# LSM303_breakout_board-v12.net
KiCad netlist of a schematic drawn in EAGLE
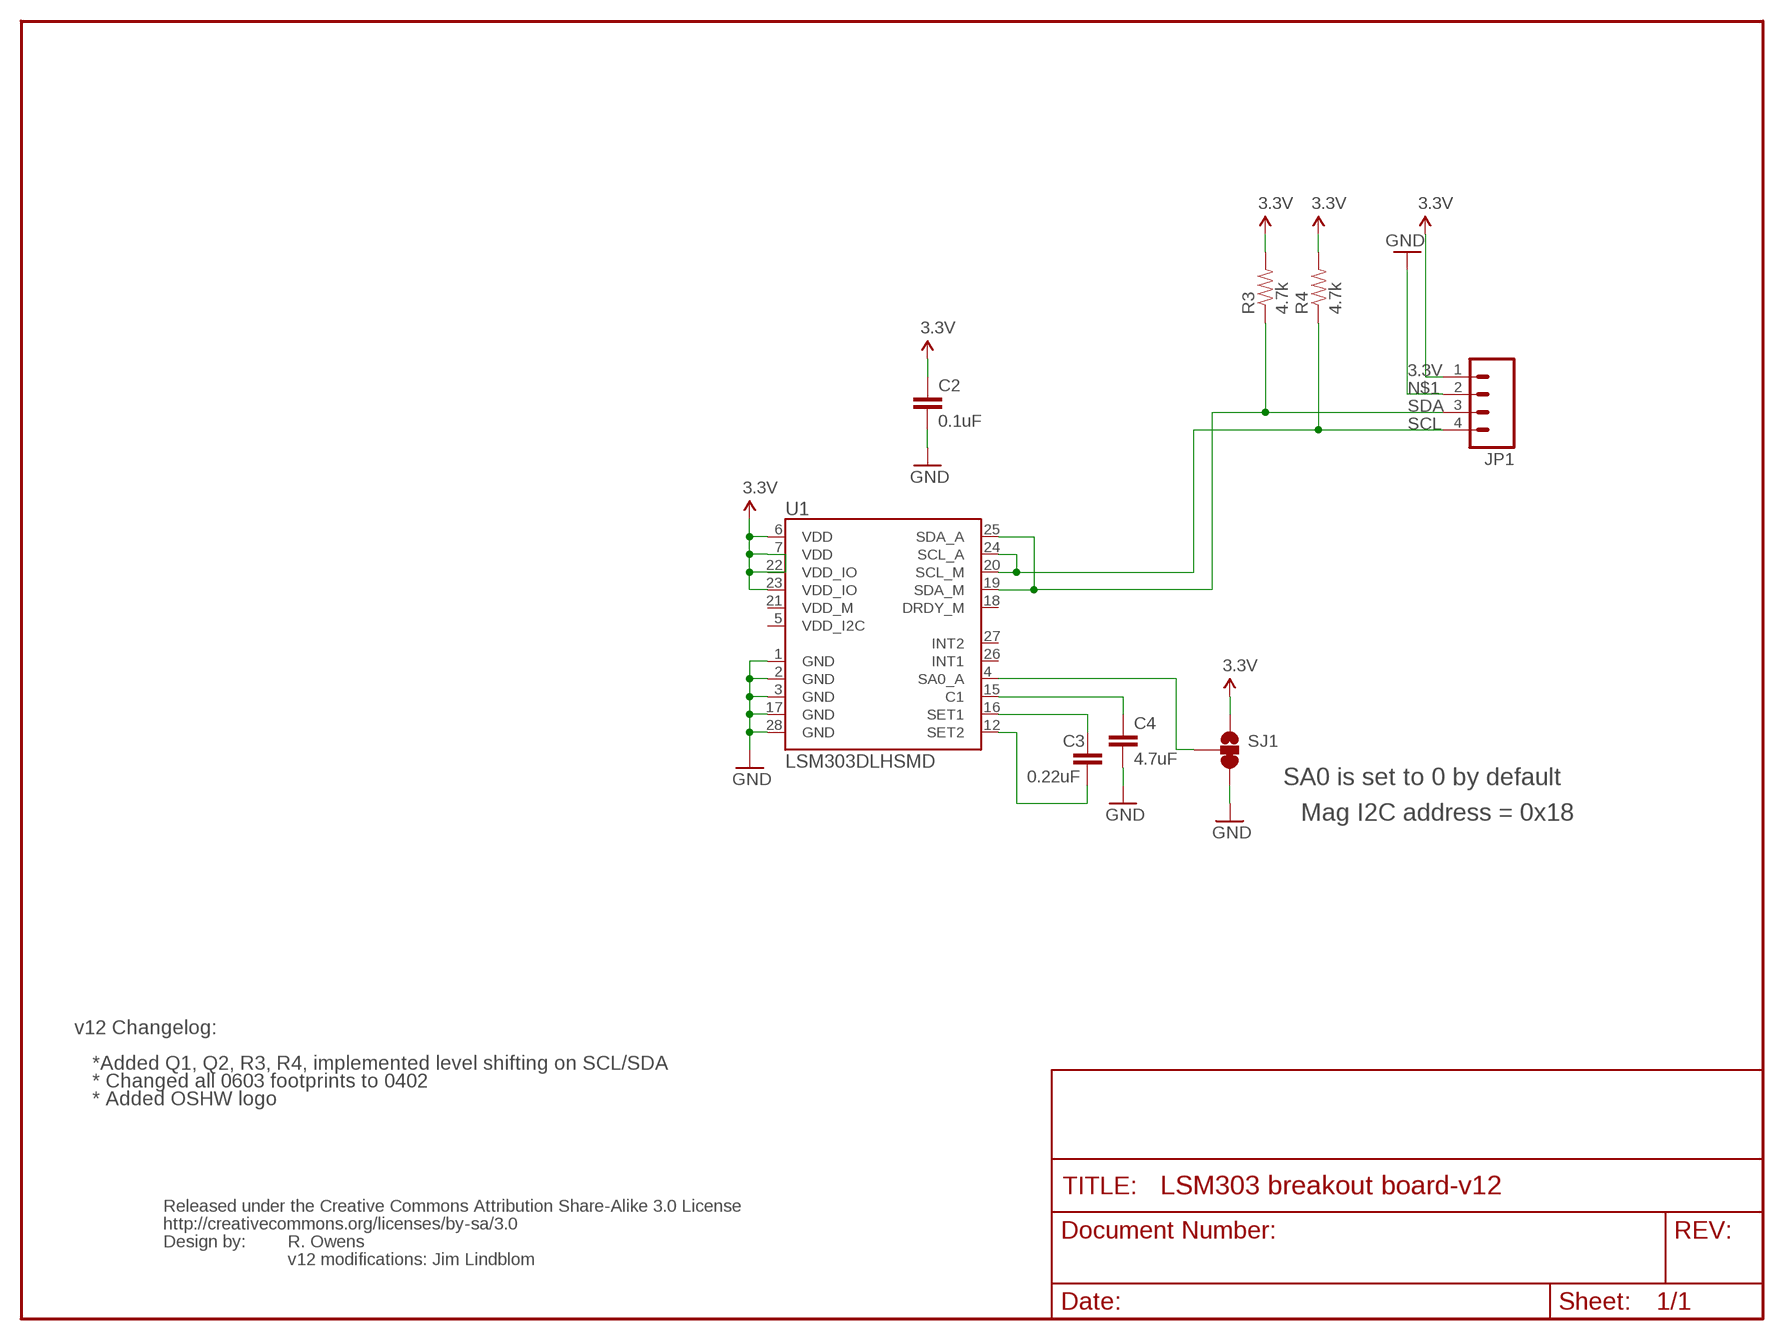
[diagram p0: schematic, sheet 1]

(export (version "E")
  (design (tool "Eeschema 10.0.6"))
  (components
    (comp (ref "C2")
      (value "0.1uF")
      (footprint "eagle-import:0603-CAP")
      (libsource (lib "eagle-import") (part "CAP0603-CAP"))
    )
    (comp (ref "C3")
      (value "0.22uF")
      (footprint "eagle-import:0603-CAP")
      (libsource (lib "eagle-import") (part "CAP0603-CAP"))
    )
    (comp (ref "C4")
      (value "4.7uF")
      (footprint "eagle-import:1206")
      (libsource (lib "eagle-import") (part "CAP1206"))
    )
    (comp (ref "JP1")
      (value "M04PTH")
      (footprint "eagle-import:1X04")
      (libsource (lib "eagle-import") (part "M04PTH"))
    )
    (comp (ref "R3")
      (value "4.7k")
      (footprint "eagle-import:0805")
      (libsource (lib "eagle-import") (part "RESISTOR0805-RES"))
    )
    (comp (ref "R4")
      (value "4.7k")
      (footprint "eagle-import:0805")
      (libsource (lib "eagle-import") (part "RESISTOR0805-RES"))
    )
    (comp (ref "SJ1")
      (value "SOLDERJUMPER_2WAYPASTE2&3")
      (footprint "eagle-import:SJ_3_PASTE2&3")
      (libsource (lib "eagle-import") (part "SOLDERJUMPER_2WAYPASTE2&3"))
    )
    (comp (ref "U$5")
      (value "CREATIVE_COMMONS")
      (footprint "eagle-import:CREATIVE_COMMONS")
      (libsource (lib "eagle-import") (part "CREATIVE_COMMONS"))
    )
    (comp (ref "U1")
      (value "LSM303DLHSMD")
      (footprint "eagle-import:LGA28-5X5")
      (libsource (lib "eagle-import") (part "LSM303DLHSMD"))
    )
  )
  (nets
    (net (code "1") (name "/SCL") (class "Default")
      (node (ref "JP1") (pin "4") (pinfunction "4_4") (pintype "passive"))
      (node (ref "R4") (pin "1") (pinfunction "1_1") (pintype "passive"))
      (node (ref "U1") (pin "20") (pinfunction "SCL_M_20") (pintype "bidirectional"))
      (node (ref "U1") (pin "24") (pinfunction "SCL_A_24") (pintype "bidirectional"))
    )
    (net (code "2") (name "/SDA") (class "Default")
      (node (ref "JP1") (pin "3") (pinfunction "3_3") (pintype "passive"))
      (node (ref "R3") (pin "1") (pinfunction "1_1") (pintype "passive"))
      (node (ref "U1") (pin "19") (pinfunction "SDA_M_19") (pintype "bidirectional"))
      (node (ref "U1") (pin "25") (pinfunction "SDA_A_25") (pintype "bidirectional"))
    )
    (net (code "3") (name "3.3V") (class "Default")
      (node (ref "C2") (pin "1") (pinfunction "1_1") (pintype "passive"))
      (node (ref "JP1") (pin "1") (pinfunction "1_1") (pintype "passive"))
      (node (ref "R3") (pin "2") (pinfunction "2_2") (pintype "passive"))
      (node (ref "R4") (pin "2") (pinfunction "2_2") (pintype "passive"))
      (node (ref "SJ1") (pin "1") (pinfunction "1_1") (pintype "passive"))
      (node (ref "U1") (pin "23") (pinfunction "VDD_IO_23") (pintype "bidirectional"))
      (node (ref "U1") (pin "6") (pinfunction "VDD_6") (pintype "bidirectional"))
      (node (ref "U1") (pin "7") (pinfunction "VDD_7") (pintype "bidirectional"))
    )
    (net (code "4") (name "GND") (class "Default")
      (node (ref "C2") (pin "2") (pinfunction "2_2") (pintype "passive"))
      (node (ref "C4") (pin "2") (pinfunction "2_2") (pintype "passive"))
      (node (ref "JP1") (pin "2") (pinfunction "2_2") (pintype "passive"))
      (node (ref "SJ1") (pin "3") (pinfunction "3_3") (pintype "passive"))
      (node (ref "U1") (pin "1") (pinfunction "GND_1") (pintype "bidirectional"))
      (node (ref "U1") (pin "17") (pinfunction "GND_17") (pintype "bidirectional"))
      (node (ref "U1") (pin "2") (pinfunction "GND_2") (pintype "bidirectional"))
      (node (ref "U1") (pin "28") (pinfunction "GND_28") (pintype "bidirectional"))
      (node (ref "U1") (pin "3") (pinfunction "GND_3") (pintype "bidirectional"))
    )
    (net (code "5") (name "Net-(U1-C1)") (class "Default")
      (node (ref "C4") (pin "1") (pinfunction "1_1") (pintype "passive"))
      (node (ref "U1") (pin "15") (pinfunction "C1_15") (pintype "bidirectional"))
    )
    (net (code "6") (name "Net-(U1-SA0_A)") (class "Default")
      (node (ref "SJ1") (pin "2") (pinfunction "2_2") (pintype "passive"))
      (node (ref "U1") (pin "4") (pinfunction "SA0_A_4") (pintype "bidirectional"))
    )
    (net (code "7") (name "Net-(U1-SET1)") (class "Default")
      (node (ref "C3") (pin "1") (pinfunction "1_1") (pintype "passive"))
      (node (ref "U1") (pin "16") (pinfunction "SET1_16") (pintype "bidirectional"))
    )
    (net (code "8") (name "Net-(U1-SET2)") (class "Default")
      (node (ref "C3") (pin "2") (pinfunction "2_2") (pintype "passive"))
      (node (ref "U1") (pin "12") (pinfunction "SET2_12") (pintype "bidirectional"))
    )
    (net (code "9") (name "unconnected-(U1-DRDY_M-Pad18)") (class "Default")
      (node (ref "U1") (pin "18") (pinfunction "DRDY_M_18") (pintype "bidirectional"))
    )
    (net (code "10") (name "unconnected-(U1-INT1-Pad26)") (class "Default")
      (node (ref "U1") (pin "26") (pinfunction "INT1_26") (pintype "bidirectional"))
    )
    (net (code "11") (name "unconnected-(U1-INT2-Pad27)") (class "Default")
      (node (ref "U1") (pin "27") (pinfunction "INT2_27") (pintype "bidirectional"))
    )
    (net (code "12") (name "unconnected-(U1-VDD_I2C-Pad5)") (class "Default")
      (node (ref "U1") (pin "5") (pinfunction "VDD_I2C_5") (pintype "bidirectional"))
    )
    (net (code "13") (name "unconnected-(U1-VDD_IO-Pad22)") (class "Default")
      (node (ref "U1") (pin "22") (pinfunction "VDD_IO_22") (pintype "bidirectional"))
    )
    (net (code "14") (name "unconnected-(U1-VDD_M-Pad21)") (class "Default")
      (node (ref "U1") (pin "21") (pinfunction "VDD_M_21") (pintype "bidirectional"))
    )
  )
)
